# SCH-4-ESC2.net
KiCad netlist of a schematic drawn in Altium Designer
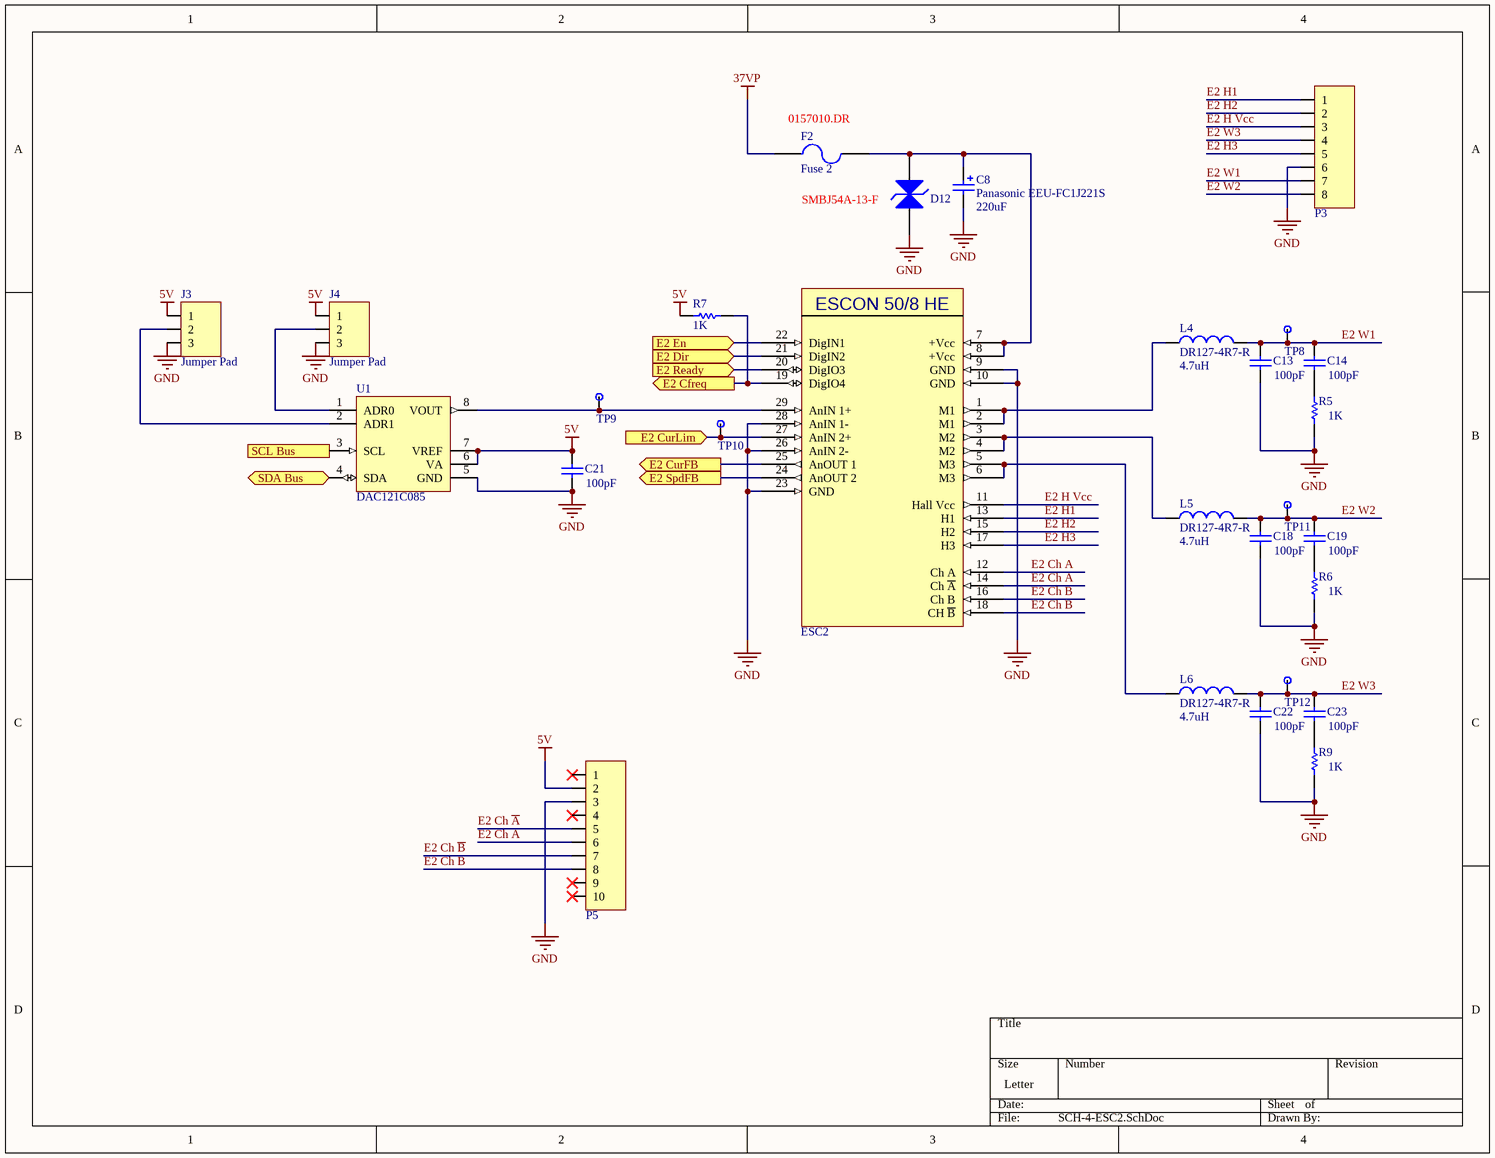
[diagram p0: SCH-4-ESC2.SchDoc]

(export (version "E")
  (design (tool "Eeschema 10.0.6"))
  (components
    (comp (ref "C8")
      (value "Panasonic EEU-FC1J221S")
      (footprint "Panasonic EEU-FC1J221S")
      (description "Polarized Capacitor (Radial)")
      (fields (field (name "ALTIUM_VALUE") "220uF"))
      (libsource (lib "RSX_Capacitors") (part "Panasonic EEU-FC1J221S"))
    )
    (comp (ref "C13")
      (value "100pF")
      (footprint "C1206")
      (description "Capacitor (Semiconductor SIM Model)")
      (fields (field (name "Comment") "Cap Semi") (field (name "PUBLISHER") "Altium Limited"))
      (libsource (lib "Miscellaneous Devices") (part "Cap Semi"))
    )
    (comp (ref "C14")
      (value "100pF")
      (footprint "C1206")
      (description "Capacitor (Semiconductor SIM Model)")
      (fields (field (name "Comment") "Cap Semi") (field (name "PUBLISHER") "Altium Limited"))
      (libsource (lib "Miscellaneous Devices") (part "Cap Semi"))
    )
    (comp (ref "C18")
      (value "100pF")
      (footprint "C1206")
      (description "Capacitor (Semiconductor SIM Model)")
      (fields (field (name "Comment") "Cap Semi") (field (name "PUBLISHER") "Altium Limited"))
      (libsource (lib "Miscellaneous Devices") (part "Cap Semi"))
    )
    (comp (ref "C19")
      (value "100pF")
      (footprint "C1206")
      (description "Capacitor (Semiconductor SIM Model)")
      (fields (field (name "Comment") "Cap Semi") (field (name "PUBLISHER") "Altium Limited"))
      (libsource (lib "Miscellaneous Devices") (part "Cap Semi"))
    )
    (comp (ref "C21")
      (value "100pF")
      (footprint "C1206")
      (description "Capacitor (Semiconductor SIM Model)")
      (fields (field (name "Comment") "Cap Semi") (field (name "PUBLISHER") "Altium Limited"))
      (libsource (lib "Miscellaneous Devices") (part "Cap Semi"))
    )
    (comp (ref "C22")
      (value "100pF")
      (footprint "C1206")
      (description "Capacitor (Semiconductor SIM Model)")
      (fields (field (name "Comment") "Cap Semi") (field (name "PUBLISHER") "Altium Limited"))
      (libsource (lib "Miscellaneous Devices") (part "Cap Semi"))
    )
    (comp (ref "C23")
      (value "100pF")
      (footprint "C1206")
      (description "Capacitor (Semiconductor SIM Model)")
      (fields (field (name "Comment") "Cap Semi") (field (name "PUBLISHER") "Altium Limited"))
      (libsource (lib "Miscellaneous Devices") (part "Cap Semi"))
    )
    (comp (ref "D12")
      (value "TVS_DIODE")
      (footprint "SMBJ54A-13-F")
      (description "TVS Diode")
      (fields (field (name "PUBLISHER") "Altium Limited"))
      (libsource (lib "RSX_Diodes") (part "TVS_DIODE"))
    )
    (comp (ref "ESC2")
      (value "ESCON 50/8 HE")
      (footprint "ESCON 50/8 HE")
      (description "ESCON Module 50/8 HE Servocontroller")
      (libsource (lib "RSX_Modules") (part "ESCON 50/8 HE"))
    )
    (comp (ref "F2")
      (value "Fuse 2")
      (footprint "0157010.DR")
      (description "Fuse")
      (fields (field (name "PUBLISHER") "Altium Limited"))
      (libsource (lib "RSX_Miscellaneous") (part "Fuse 2"))
    )
    (comp (ref "J3")
      (value "Jumper Pad")
      (footprint "3 Pad TH")
      (libsource (lib "RSX_Test_Points") (part "3 Pad Jump Sel"))
    )
    (comp (ref "J4")
      (value "Jumper Pad")
      (footprint "3 Pad TH")
      (libsource (lib "RSX_Test_Points") (part "3 Pad Jump Sel"))
    )
    (comp (ref "L4")
      (value "DR127-4R7-R")
      (footprint "DR127-4R7-R")
      (description "4.7µH Shielded Wirewound Inductor 8.25A 9.17mOhm Nonstandard")
      (fields (field (name "ALTIUM_VALUE") "4.7uH") (field (name "PUBLISHER") "Altium Limited"))
      (libsource (lib "RSX_Inductors") (part "DR127-4R7-R"))
    )
    (comp (ref "L5")
      (value "DR127-4R7-R")
      (footprint "DR127-4R7-R")
      (description "4.7µH Shielded Wirewound Inductor 8.25A 9.17mOhm Nonstandard")
      (fields (field (name "ALTIUM_VALUE") "4.7uH") (field (name "PUBLISHER") "Altium Limited"))
      (libsource (lib "RSX_Inductors") (part "DR127-4R7-R"))
    )
    (comp (ref "L6")
      (value "DR127-4R7-R")
      (footprint "DR127-4R7-R")
      (description "4.7µH Shielded Wirewound Inductor 8.25A 9.17mOhm Nonstandard")
      (fields (field (name "ALTIUM_VALUE") "4.7uH") (field (name "PUBLISHER") "Altium Limited"))
      (libsource (lib "RSX_Inductors") (part "DR127-4R7-R"))
    )
    (comp (ref "P3")
      (value "Mini-Fit Jr 8 Pos")
      (footprint "Molex Mini-Fit Jr 0039281083")
      (libsource (lib "RSX_Connectors") (part "Molex Mini-Fit Jr 8pos Vert"))
    )
    (comp (ref "P5")
      (value "Header_10_Pos_Ribbon Male")
      (footprint "3M_2510-6002UB")
      (description "3M_2510-6002UB")
      (libsource (lib "RSX_Connectors") (part "Header_10_Pos_Ribbon Male"))
    )
    (comp (ref "R5")
      (value "1K")
      (footprint "RESC1608X06N_0603")
      (description "Resistor")
      (fields (field (name "Comment") "Res1") (field (name "PUBLISHER") "Altium Limited"))
      (libsource (lib "RSX_Resistors") (part "Res1"))
    )
    (comp (ref "R6")
      (value "1K")
      (footprint "RESC1608X06N_0603")
      (description "Resistor")
      (fields (field (name "Comment") "Res1") (field (name "PUBLISHER") "Altium Limited"))
      (libsource (lib "RSX_Resistors") (part "Res1"))
    )
    (comp (ref "R7")
      (value "1K")
      (footprint "RESC1608X06N_0603")
      (description "Resistor")
      (fields (field (name "Comment") "Res1") (field (name "PUBLISHER") "Altium Limited"))
      (libsource (lib "RSX_Resistors") (part "Res1"))
    )
    (comp (ref "R9")
      (value "1K")
      (footprint "RESC1608X06N_0603")
      (description "Resistor")
      (fields (field (name "Comment") "Res1") (field (name "PUBLISHER") "Altium Limited"))
      (libsource (lib "RSX_Resistors") (part "Res1"))
    )
    (comp (ref "TP8")
      (value "TestPt")
      (footprint "50_MIL_PAD")
      (libsource (lib "RSX_Test_Points") (part "TestPt"))
    )
    (comp (ref "TP9")
      (value "TestPt")
      (footprint "50_MIL_PAD")
      (libsource (lib "RSX_Test_Points") (part "TestPt"))
    )
    (comp (ref "TP10")
      (value "TestPt")
      (footprint "50_MIL_PAD")
      (libsource (lib "RSX_Test_Points") (part "TestPt"))
    )
    (comp (ref "TP11")
      (value "TestPt")
      (footprint "50_MIL_PAD")
      (libsource (lib "RSX_Test_Points") (part "TestPt"))
    )
    (comp (ref "TP12")
      (value "TestPt")
      (footprint "50_MIL_PAD")
      (libsource (lib "RSX_Test_Points") (part "TestPt"))
    )
    (comp (ref "U1")
      (value "DAC121C085")
      (footprint "MUA08A_L")
      (fields (field (name "MANUFACTURER") "National Semiconductor"))
      (libsource (lib "RSX_Schematics") (part "DAC121C085"))
    )
  )
  (nets
    (net (code "1") (name "/E2 Cfreq") (class "Default")
      (node (ref "ESC2") (pin "19") (pinfunction "DigIO4_19") (pintype "bidirectional"))
      (node (ref "R7") (pin "1") (pinfunction "1_1") (pintype "passive"))
    )
    (net (code "2") (name "/E2 Ch A") (class "Default")
      (node (ref "ESC2") (pin "12") (pinfunction "Ch_A_12") (pintype "input"))
      (node (ref "P5") (pin "6") (pinfunction "6_6") (pintype "passive"))
    )
    (net (code "3") (name "/E2 Ch B") (class "Default")
      (node (ref "ESC2") (pin "16") (pinfunction "Ch_B_16") (pintype "input"))
      (node (ref "P5") (pin "8") (pinfunction "8_8") (pintype "passive"))
    )
    (net (code "4") (name "/E2 Ch ~{A}") (class "Default")
      (node (ref "ESC2") (pin "14") (pinfunction "Ch_~{A}_14") (pintype "input"))
      (node (ref "P5") (pin "5") (pinfunction "5_5") (pintype "passive"))
    )
    (net (code "5") (name "/E2 Ch ~{B}") (class "Default")
      (node (ref "ESC2") (pin "18") (pinfunction "CH_~{B}_18") (pintype "input"))
      (node (ref "P5") (pin "7") (pinfunction "7_7") (pintype "passive"))
    )
    (net (code "6") (name "/E2 CurFB") (class "Default")
      (node (ref "ESC2") (pin "25") (pinfunction "AnOUT_1_25") (pintype "output"))
    )
    (net (code "7") (name "/E2 CurLim") (class "Default")
      (node (ref "ESC2") (pin "27") (pinfunction "AnIN_2+_27") (pintype "input"))
      (node (ref "TP10") (pin "1") (pinfunction "1_1") (pintype "passive"))
    )
    (net (code "8") (name "/E2 Dir") (class "Default")
      (node (ref "ESC2") (pin "21") (pinfunction "DigIN2_21") (pintype "input"))
    )
    (net (code "9") (name "/E2 En") (class "Default")
      (node (ref "ESC2") (pin "22") (pinfunction "DigIN1_22") (pintype "input"))
    )
    (net (code "10") (name "/E2 H Vcc") (class "Default")
      (node (ref "ESC2") (pin "11") (pinfunction "Hall_Vcc_11") (pintype "output"))
      (node (ref "P3") (pin "3") (pinfunction "3_3") (pintype "passive"))
    )
    (net (code "11") (name "/E2 H1") (class "Default")
      (node (ref "ESC2") (pin "13") (pinfunction "H1_13") (pintype "input"))
      (node (ref "P3") (pin "1") (pinfunction "1_1") (pintype "passive"))
    )
    (net (code "12") (name "/E2 H2") (class "Default")
      (node (ref "ESC2") (pin "15") (pinfunction "H2_15") (pintype "input"))
      (node (ref "P3") (pin "2") (pinfunction "2_2") (pintype "passive"))
    )
    (net (code "13") (name "/E2 H3") (class "Default")
      (node (ref "ESC2") (pin "17") (pinfunction "H3_17") (pintype "input"))
      (node (ref "P3") (pin "5") (pinfunction "5_5") (pintype "passive"))
    )
    (net (code "14") (name "/E2 Ready") (class "Default")
      (node (ref "ESC2") (pin "20") (pinfunction "DigIO3_20") (pintype "bidirectional"))
    )
    (net (code "15") (name "/E2 SpdFB") (class "Default")
      (node (ref "ESC2") (pin "24") (pinfunction "AnOUT_2_24") (pintype "output"))
    )
    (net (code "16") (name "/E2 W1") (class "Default")
      (node (ref "C13") (pin "2") (pinfunction "2_2") (pintype "passive"))
      (node (ref "C14") (pin "2") (pinfunction "2_2") (pintype "passive"))
      (node (ref "L4") (pin "2") (pinfunction "2_2") (pintype "passive"))
      (node (ref "P3") (pin "7") (pinfunction "7_7") (pintype "passive"))
      (node (ref "TP8") (pin "1") (pinfunction "1_1") (pintype "passive"))
    )
    (net (code "17") (name "/E2 W2") (class "Default")
      (node (ref "C18") (pin "2") (pinfunction "2_2") (pintype "passive"))
      (node (ref "C19") (pin "2") (pinfunction "2_2") (pintype "passive"))
      (node (ref "L5") (pin "2") (pinfunction "2_2") (pintype "passive"))
      (node (ref "P3") (pin "8") (pinfunction "8_8") (pintype "passive"))
      (node (ref "TP11") (pin "1") (pinfunction "1_1") (pintype "passive"))
    )
    (net (code "18") (name "/E2 W3") (class "Default")
      (node (ref "C22") (pin "2") (pinfunction "2_2") (pintype "passive"))
      (node (ref "C23") (pin "2") (pinfunction "2_2") (pintype "passive"))
      (node (ref "L6") (pin "2") (pinfunction "2_2") (pintype "passive"))
      (node (ref "P3") (pin "4") (pinfunction "4_4") (pintype "passive"))
      (node (ref "TP12") (pin "1") (pinfunction "1_1") (pintype "passive"))
    )
    (net (code "19") (name "/SCL Bus") (class "Default")
      (node (ref "U1") (pin "3") (pinfunction "SCL_3") (pintype "input"))
    )
    (net (code "20") (name "/SDA Bus") (class "Default")
      (node (ref "U1") (pin "4") (pinfunction "SDA_4") (pintype "bidirectional"))
    )
    (net (code "21") (name "5V") (class "Default")
      (node (ref "C21") (pin "2") (pinfunction "2_2") (pintype "passive"))
      (node (ref "J3") (pin "1") (pinfunction "1_1") (pintype "passive"))
      (node (ref "J4") (pin "1") (pinfunction "1_1") (pintype "passive"))
      (node (ref "P5") (pin "2") (pinfunction "2_2") (pintype "passive"))
      (node (ref "R7") (pin "2") (pinfunction "2_2") (pintype "passive"))
      (node (ref "U1") (pin "6") (pinfunction "VA_6") (pintype "power_in"))
      (node (ref "U1") (pin "7") (pinfunction "VREF_7") (pintype "power_in"))
    )
    (net (code "22") (name "37VP") (class "Default")
      (node (ref "F2") (pin "1") (pinfunction "1_1") (pintype "passive"))
    )
    (net (code "23") (name "GND") (class "Default")
      (node (ref "C13") (pin "1") (pinfunction "1_1") (pintype "passive"))
      (node (ref "C18") (pin "1") (pinfunction "1_1") (pintype "passive"))
      (node (ref "C21") (pin "1") (pinfunction "1_1") (pintype "passive"))
      (node (ref "C22") (pin "1") (pinfunction "1_1") (pintype "passive"))
      (node (ref "C8") (pin "2") (pinfunction "2_2") (pintype "passive"))
      (node (ref "D12") (pin "1") (pinfunction "A_1") (pintype "passive"))
      (node (ref "ESC2") (pin "10") (pinfunction "GND_10") (pintype "input"))
      (node (ref "ESC2") (pin "23") (pinfunction "GND_23") (pintype "input"))
      (node (ref "ESC2") (pin "26") (pinfunction "AnIN_2-_26") (pintype "input"))
      (node (ref "ESC2") (pin "28") (pinfunction "AnIN_1-_28") (pintype "input"))
      (node (ref "ESC2") (pin "9") (pinfunction "GND_9") (pintype "input"))
      (node (ref "J3") (pin "3") (pinfunction "3_3") (pintype "passive"))
      (node (ref "J4") (pin "3") (pinfunction "3_3") (pintype "passive"))
      (node (ref "P3") (pin "6") (pinfunction "6_6") (pintype "passive"))
      (node (ref "P5") (pin "3") (pinfunction "3_3") (pintype "passive"))
      (node (ref "R5") (pin "1") (pinfunction "1_1") (pintype "passive"))
      (node (ref "R6") (pin "1") (pinfunction "1_1") (pintype "passive"))
      (node (ref "R9") (pin "1") (pinfunction "1_1") (pintype "passive"))
      (node (ref "U1") (pin "5") (pinfunction "GND_5") (pintype "power_in"))
    )
    (net (code "24") (name "Net-(C14-Pad1)") (class "Default")
      (node (ref "C14") (pin "1") (pinfunction "1_1") (pintype "passive"))
      (node (ref "R5") (pin "2") (pinfunction "2_2") (pintype "passive"))
    )
    (net (code "25") (name "Net-(C19-Pad1)") (class "Default")
      (node (ref "C19") (pin "1") (pinfunction "1_1") (pintype "passive"))
      (node (ref "R6") (pin "2") (pinfunction "2_2") (pintype "passive"))
    )
    (net (code "26") (name "Net-(C23-Pad1)") (class "Default")
      (node (ref "C23") (pin "1") (pinfunction "1_1") (pintype "passive"))
      (node (ref "R9") (pin "2") (pinfunction "2_2") (pintype "passive"))
    )
    (net (code "27") (name "Net-(D12-K)") (class "Default")
      (node (ref "C8") (pin "1") (pinfunction "1_1") (pintype "passive"))
      (node (ref "D12") (pin "2") (pinfunction "K_2") (pintype "passive"))
      (node (ref "ESC2") (pin "7") (pinfunction "+Vcc_7") (pintype "input"))
      (node (ref "ESC2") (pin "8") (pinfunction "+Vcc_8") (pintype "input"))
      (node (ref "F2") (pin "2") (pinfunction "2_2") (pintype "passive"))
    )
    (net (code "28") (name "Net-(ESC2-AnIN_1+)") (class "Default")
      (node (ref "ESC2") (pin "29") (pinfunction "AnIN_1+_29") (pintype "input"))
      (node (ref "TP9") (pin "1") (pinfunction "1_1") (pintype "passive"))
      (node (ref "U1") (pin "8") (pinfunction "VOUT_8") (pintype "output"))
    )
    (net (code "29") (name "Net-(ESC2-M1-Pad1)") (class "Default")
      (node (ref "ESC2") (pin "1") (pinfunction "M1_1") (pintype "output"))
      (node (ref "ESC2") (pin "2") (pinfunction "M1_2") (pintype "output"))
      (node (ref "L4") (pin "1") (pinfunction "1_1") (pintype "passive"))
    )
    (net (code "30") (name "Net-(ESC2-M2-Pad3)") (class "Default")
      (node (ref "ESC2") (pin "3") (pinfunction "M2_3") (pintype "output"))
      (node (ref "ESC2") (pin "4") (pinfunction "M2_4") (pintype "output"))
      (node (ref "L5") (pin "1") (pinfunction "1_1") (pintype "passive"))
    )
    (net (code "31") (name "Net-(ESC2-M3-Pad5)") (class "Default")
      (node (ref "ESC2") (pin "5") (pinfunction "M3_5") (pintype "output"))
      (node (ref "ESC2") (pin "6") (pinfunction "M3_6") (pintype "output"))
      (node (ref "L6") (pin "1") (pinfunction "1_1") (pintype "passive"))
    )
    (net (code "32") (name "Net-(U1-ADR0)") (class "Default")
      (node (ref "J4") (pin "2") (pinfunction "2_2") (pintype "passive"))
      (node (ref "U1") (pin "1") (pinfunction "ADR0_1") (pintype "tri_state"))
    )
    (net (code "33") (name "Net-(U1-ADR1)") (class "Default")
      (node (ref "J3") (pin "2") (pinfunction "2_2") (pintype "passive"))
      (node (ref "U1") (pin "2") (pinfunction "ADR1_2") (pintype "tri_state"))
    )
    (net (code "34") (name "unconnected-(P5-Pad1)") (class "Default")
      (node (ref "P5") (pin "1") (pinfunction "1_1") (pintype "passive+no_connect"))
    )
    (net (code "35") (name "unconnected-(P5-Pad4)") (class "Default")
      (node (ref "P5") (pin "4") (pinfunction "4_4") (pintype "passive+no_connect"))
    )
    (net (code "36") (name "unconnected-(P5-Pad9)") (class "Default")
      (node (ref "P5") (pin "9") (pinfunction "9_9") (pintype "passive+no_connect"))
    )
    (net (code "37") (name "unconnected-(P5-Pad10)") (class "Default")
      (node (ref "P5") (pin "10") (pinfunction "10_10") (pintype "passive+no_connect"))
    )
  )
)
